# card_shield.net
KiCad netlist of a schematic drawn in EAGLE
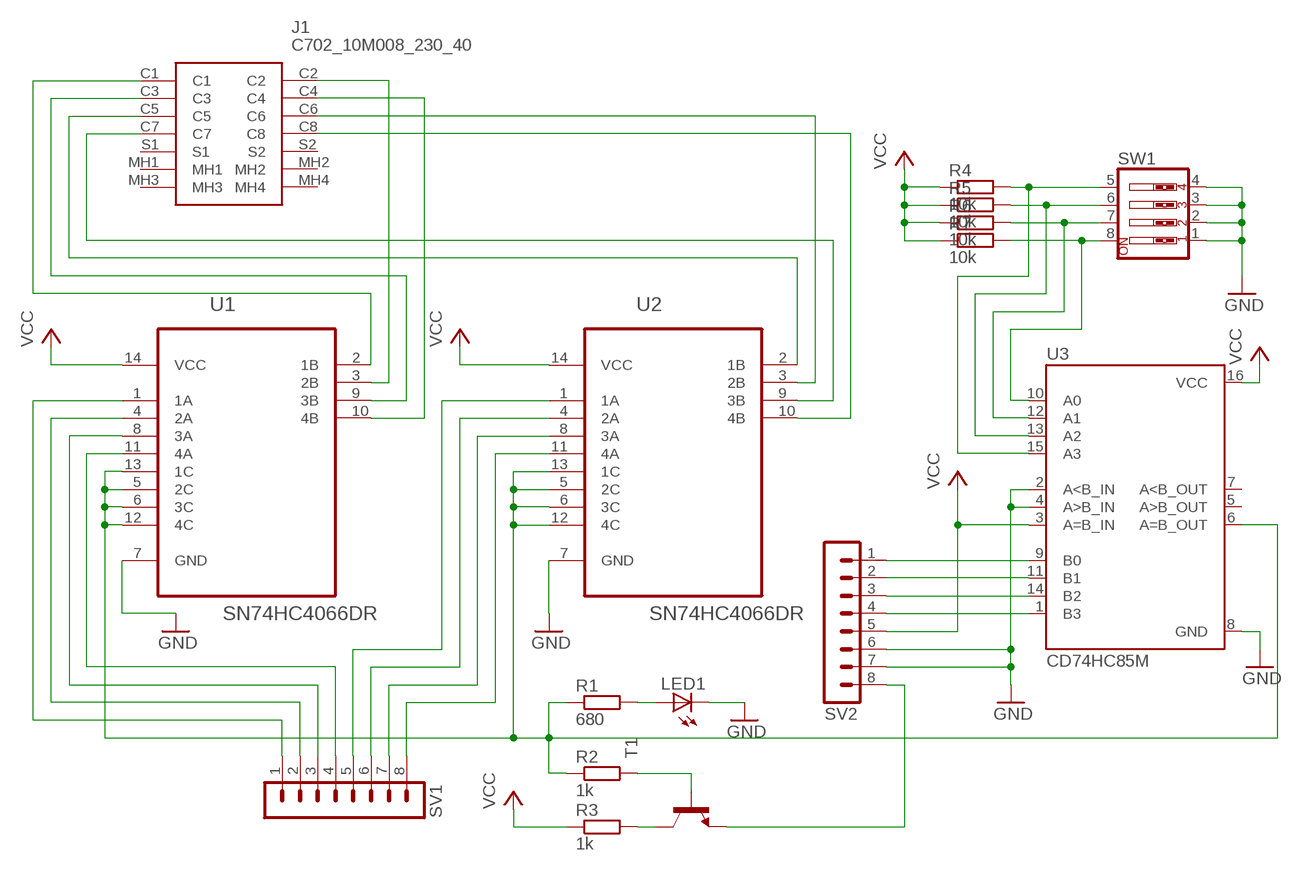
[diagram p0: schematic, sheet 1]

(export (version "E")
  (design (tool "Eeschema 10.0.6"))
  (components
    (comp (ref "J1")
      (value "C702_10M008_230_40")
      (footprint "eagle-import:C70210M00823040")
      (fields
        (field (name "MANUFACTURER_PART_NUMBER") "C702 10M008 230 40")
        (field (name "MOUSER_PART_NUMBER") "523-C70210M00823040")
      )
      (libsource (lib "eagle-import") (part "C702_10M008_230_40"))
    )
    (comp (ref "LED1")
      (value "LEDSML1206")
      (footprint "eagle-import:SML1206")
      (libsource (lib "eagle-import") (part "LEDSML1206"))
    )
    (comp (ref "R1")
      (value "680")
      (footprint "eagle-import:R0805")
      (libsource (lib "eagle-import") (part "R-EU_R0805"))
    )
    (comp (ref "R2")
      (value "1k")
      (footprint "eagle-import:R0805")
      (libsource (lib "eagle-import") (part "R-EU_R0805"))
    )
    (comp (ref "R3")
      (value "1k")
      (footprint "eagle-import:R0805")
      (libsource (lib "eagle-import") (part "R-EU_R0805"))
    )
    (comp (ref "R4")
      (value "10k")
      (footprint "eagle-import:R0805")
      (libsource (lib "eagle-import") (part "R-EU_R0805"))
    )
    (comp (ref "R5")
      (value "10k")
      (footprint "eagle-import:R0805")
      (libsource (lib "eagle-import") (part "R-EU_R0805"))
    )
    (comp (ref "R6")
      (value "10k")
      (footprint "eagle-import:R0805")
      (libsource (lib "eagle-import") (part "R-EU_R0805"))
    )
    (comp (ref "R7")
      (value "10k")
      (footprint "eagle-import:R0805")
      (libsource (lib "eagle-import") (part "R-EU_R0805"))
    )
    (comp (ref "SV1")
      (value "MA08-1")
      (footprint "eagle-import:MA08-1")
      (libsource (lib "eagle-import") (part "MA08-1"))
    )
    (comp (ref "SV2")
      (value "MA08-1")
      (footprint "eagle-import:MA08-1")
      (libsource (lib "eagle-import") (part "MA08-1"))
    )
    (comp (ref "SW1")
      (value "SW_DIP-4")
      (footprint "eagle-import:EDG-04")
      (libsource (lib "eagle-import") (part "SW_DIP-4"))
    )
    (comp (ref "T1")
      (value "BC817-16-NPN-SOT23-BEC")
      (footprint "eagle-import:SOT23-BEC")
      (libsource (lib "eagle-import") (part "-NPN-SOT23-BECBC817-16"))
    )
    (comp (ref "U1")
      (value "SN74HC4066DR")
      (footprint "eagle-import:SOIC127P600X175-14N")
      (fields (field (name "MF") "Texas Instruments"))
      (libsource (lib "eagle-import") (part "SN74HC4066DR"))
    )
    (comp (ref "U2")
      (value "SN74HC4066DR")
      (footprint "eagle-import:SOIC127P600X175-14N")
      (fields (field (name "MF") "Texas Instruments"))
      (libsource (lib "eagle-import") (part "SN74HC4066DR"))
    )
    (comp (ref "U3")
      (value "CD74HC85M")
      (footprint "eagle-import:SOIC12P600X175-16N")
      (fields (field (name "MF") "Texas Instruments"))
      (libsource (lib "eagle-import") (part "CD74HC85M"))
    )
  )
  (nets
    (net (code "1") (name "GND") (class "Default")
      (node (ref "LED1") (pin "C") (pinfunction "C_C") (pintype "passive"))
      (node (ref "SV2") (pin "6") (pinfunction "6_6") (pintype "passive"))
      (node (ref "SV2") (pin "7") (pinfunction "7_7") (pintype "passive"))
      (node (ref "SW1") (pin "1") (pinfunction "1_1") (pintype "passive"))
      (node (ref "SW1") (pin "2") (pinfunction "2_2") (pintype "passive"))
      (node (ref "SW1") (pin "3") (pinfunction "3_3") (pintype "passive"))
      (node (ref "SW1") (pin "4") (pinfunction "4_4") (pintype "passive"))
      (node (ref "U1") (pin "7") (pinfunction "GND_7") (pintype "passive"))
      (node (ref "U2") (pin "7") (pinfunction "GND_7") (pintype "passive"))
      (node (ref "U3") (pin "2") (pinfunction "A<B_IN_2") (pintype "input"))
      (node (ref "U3") (pin "4") (pinfunction "A>B_IN_4") (pintype "input"))
      (node (ref "U3") (pin "8") (pinfunction "GND_8") (pintype "power_in"))
    )
    (net (code "2") (name "Net-(LED1-PadA)") (class "Default")
      (node (ref "LED1") (pin "A") (pinfunction "A_A") (pintype "passive"))
      (node (ref "R1") (pin "2") (pinfunction "2_2") (pintype "passive"))
    )
    (net (code "3") (name "Net-(R2-Pad2)") (class "Default")
      (node (ref "R2") (pin "2") (pinfunction "2_2") (pintype "passive"))
      (node (ref "T1") (pin "B") (pinfunction "B_B") (pintype "passive"))
    )
    (net (code "4") (name "Net-(R3-Pad2)") (class "Default")
      (node (ref "R3") (pin "2") (pinfunction "2_2") (pintype "passive"))
      (node (ref "T1") (pin "C") (pinfunction "C_C") (pintype "passive"))
    )
    (net (code "5") (name "Net-(SV2-Pad8)") (class "Default")
      (node (ref "SV2") (pin "8") (pinfunction "8_8") (pintype "passive"))
      (node (ref "T1") (pin "E") (pinfunction "E_E") (pintype "passive"))
    )
    (net (code "6") (name "Net-(U1-1A)") (class "Default")
      (node (ref "SV1") (pin "1") (pinfunction "1_1") (pintype "passive"))
      (node (ref "U1") (pin "1") (pinfunction "1A_1") (pintype "input"))
    )
    (net (code "7") (name "Net-(U1-1B)") (class "Default")
      (node (ref "J1") (pin "C1") (pinfunction "C1_C1") (pintype "bidirectional"))
      (node (ref "U1") (pin "2") (pinfunction "1B_2") (pintype "output"))
    )
    (net (code "8") (name "Net-(U1-1C)") (class "Default")
      (node (ref "R1") (pin "1") (pinfunction "1_1") (pintype "passive"))
      (node (ref "R2") (pin "1") (pinfunction "1_1") (pintype "passive"))
      (node (ref "U1") (pin "12") (pinfunction "4C_12") (pintype "input"))
      (node (ref "U1") (pin "13") (pinfunction "1C_13") (pintype "input"))
      (node (ref "U1") (pin "5") (pinfunction "2C_5") (pintype "input"))
      (node (ref "U1") (pin "6") (pinfunction "3C_6") (pintype "input"))
      (node (ref "U2") (pin "12") (pinfunction "4C_12") (pintype "input"))
      (node (ref "U2") (pin "13") (pinfunction "1C_13") (pintype "input"))
      (node (ref "U2") (pin "5") (pinfunction "2C_5") (pintype "input"))
      (node (ref "U2") (pin "6") (pinfunction "3C_6") (pintype "input"))
      (node (ref "U3") (pin "6") (pinfunction "A=B_OUT_6") (pintype "output"))
    )
    (net (code "9") (name "Net-(U1-2A)") (class "Default")
      (node (ref "SV1") (pin "2") (pinfunction "2_2") (pintype "passive"))
      (node (ref "U1") (pin "4") (pinfunction "2A_4") (pintype "input"))
    )
    (net (code "10") (name "Net-(U1-2B)") (class "Default")
      (node (ref "J1") (pin "C2") (pinfunction "C2_C2") (pintype "bidirectional"))
      (node (ref "U1") (pin "3") (pinfunction "2B_3") (pintype "output"))
    )
    (net (code "11") (name "Net-(U1-3A)") (class "Default")
      (node (ref "SV1") (pin "3") (pinfunction "3_3") (pintype "passive"))
      (node (ref "U1") (pin "8") (pinfunction "3A_8") (pintype "input"))
    )
    (net (code "12") (name "Net-(U1-3B)") (class "Default")
      (node (ref "J1") (pin "C3") (pinfunction "C3_C3") (pintype "bidirectional"))
      (node (ref "U1") (pin "9") (pinfunction "3B_9") (pintype "output"))
    )
    (net (code "13") (name "Net-(U1-4A)") (class "Default")
      (node (ref "SV1") (pin "4") (pinfunction "4_4") (pintype "passive"))
      (node (ref "U1") (pin "11") (pinfunction "4A_11") (pintype "input"))
    )
    (net (code "14") (name "Net-(U1-4B)") (class "Default")
      (node (ref "J1") (pin "C4") (pinfunction "C4_C4") (pintype "bidirectional"))
      (node (ref "U1") (pin "10") (pinfunction "4B_10") (pintype "output"))
    )
    (net (code "15") (name "Net-(U2-1A)") (class "Default")
      (node (ref "SV1") (pin "5") (pinfunction "5_5") (pintype "passive"))
      (node (ref "U2") (pin "1") (pinfunction "1A_1") (pintype "input"))
    )
    (net (code "16") (name "Net-(U2-1B)") (class "Default")
      (node (ref "J1") (pin "C5") (pinfunction "C5_C5") (pintype "bidirectional"))
      (node (ref "U2") (pin "2") (pinfunction "1B_2") (pintype "output"))
    )
    (net (code "17") (name "Net-(U2-2A)") (class "Default")
      (node (ref "SV1") (pin "6") (pinfunction "6_6") (pintype "passive"))
      (node (ref "U2") (pin "4") (pinfunction "2A_4") (pintype "input"))
    )
    (net (code "18") (name "Net-(U2-2B)") (class "Default")
      (node (ref "J1") (pin "C6") (pinfunction "C6_C6") (pintype "bidirectional"))
      (node (ref "U2") (pin "3") (pinfunction "2B_3") (pintype "output"))
    )
    (net (code "19") (name "Net-(U2-3A)") (class "Default")
      (node (ref "SV1") (pin "7") (pinfunction "7_7") (pintype "passive"))
      (node (ref "U2") (pin "8") (pinfunction "3A_8") (pintype "input"))
    )
    (net (code "20") (name "Net-(U2-3B)") (class "Default")
      (node (ref "J1") (pin "C7") (pinfunction "C7_C7") (pintype "bidirectional"))
      (node (ref "U2") (pin "9") (pinfunction "3B_9") (pintype "output"))
    )
    (net (code "21") (name "Net-(U2-4A)") (class "Default")
      (node (ref "SV1") (pin "8") (pinfunction "8_8") (pintype "passive"))
      (node (ref "U2") (pin "11") (pinfunction "4A_11") (pintype "input"))
    )
    (net (code "22") (name "Net-(U2-4B)") (class "Default")
      (node (ref "J1") (pin "C8") (pinfunction "C8_C8") (pintype "bidirectional"))
      (node (ref "U2") (pin "10") (pinfunction "4B_10") (pintype "output"))
    )
    (net (code "23") (name "Net-(U3-A0)") (class "Default")
      (node (ref "R7") (pin "2") (pinfunction "2_2") (pintype "passive"))
      (node (ref "SW1") (pin "8") (pinfunction "8_8") (pintype "passive"))
      (node (ref "U3") (pin "10") (pinfunction "A0_10") (pintype "input"))
    )
    (net (code "24") (name "Net-(U3-A1)") (class "Default")
      (node (ref "R6") (pin "2") (pinfunction "2_2") (pintype "passive"))
      (node (ref "SW1") (pin "7") (pinfunction "7_7") (pintype "passive"))
      (node (ref "U3") (pin "12") (pinfunction "A1_12") (pintype "input"))
    )
    (net (code "25") (name "Net-(U3-A2)") (class "Default")
      (node (ref "R5") (pin "2") (pinfunction "2_2") (pintype "passive"))
      (node (ref "SW1") (pin "6") (pinfunction "6_6") (pintype "passive"))
      (node (ref "U3") (pin "13") (pinfunction "A2_13") (pintype "input"))
    )
    (net (code "26") (name "Net-(U3-A3)") (class "Default")
      (node (ref "R4") (pin "2") (pinfunction "2_2") (pintype "passive"))
      (node (ref "SW1") (pin "5") (pinfunction "5_5") (pintype "passive"))
      (node (ref "U3") (pin "15") (pinfunction "A3_15") (pintype "input"))
    )
    (net (code "27") (name "Net-(U3-B0)") (class "Default")
      (node (ref "SV2") (pin "1") (pinfunction "1_1") (pintype "passive"))
      (node (ref "U3") (pin "9") (pinfunction "B0_9") (pintype "input"))
    )
    (net (code "28") (name "Net-(U3-B1)") (class "Default")
      (node (ref "SV2") (pin "2") (pinfunction "2_2") (pintype "passive"))
      (node (ref "U3") (pin "11") (pinfunction "B1_11") (pintype "input"))
    )
    (net (code "29") (name "Net-(U3-B2)") (class "Default")
      (node (ref "SV2") (pin "3") (pinfunction "3_3") (pintype "passive"))
      (node (ref "U3") (pin "14") (pinfunction "B2_14") (pintype "input"))
    )
    (net (code "30") (name "Net-(U3-B3)") (class "Default")
      (node (ref "SV2") (pin "4") (pinfunction "4_4") (pintype "passive"))
      (node (ref "U3") (pin "1") (pinfunction "B3_1") (pintype "input"))
    )
    (net (code "31") (name "VCC") (class "Default")
      (node (ref "R3") (pin "1") (pinfunction "1_1") (pintype "passive"))
      (node (ref "R4") (pin "1") (pinfunction "1_1") (pintype "passive"))
      (node (ref "R5") (pin "1") (pinfunction "1_1") (pintype "passive"))
      (node (ref "R6") (pin "1") (pinfunction "1_1") (pintype "passive"))
      (node (ref "R7") (pin "1") (pinfunction "1_1") (pintype "passive"))
      (node (ref "SV2") (pin "5") (pinfunction "5_5") (pintype "passive"))
      (node (ref "U1") (pin "14") (pinfunction "VCC_14") (pintype "power_in"))
      (node (ref "U2") (pin "14") (pinfunction "VCC_14") (pintype "power_in"))
      (node (ref "U3") (pin "16") (pinfunction "VCC_16") (pintype "power_in"))
      (node (ref "U3") (pin "3") (pinfunction "A=B_IN_3") (pintype "input"))
    )
    (net (code "32") (name "unconnected-(J1-PadMH1)") (class "Default")
      (node (ref "J1") (pin "MH1") (pinfunction "MH1_MH1") (pintype "bidirectional"))
    )
    (net (code "33") (name "unconnected-(J1-PadMH2)") (class "Default")
      (node (ref "J1") (pin "MH2") (pinfunction "MH2_MH2") (pintype "bidirectional"))
    )
    (net (code "34") (name "unconnected-(J1-PadMH3)") (class "Default")
      (node (ref "J1") (pin "MH3") (pinfunction "MH3_MH3") (pintype "bidirectional"))
    )
    (net (code "35") (name "unconnected-(J1-PadMH4)") (class "Default")
      (node (ref "J1") (pin "MH4") (pinfunction "MH4_MH4") (pintype "bidirectional"))
    )
    (net (code "36") (name "unconnected-(J1-PadS1)") (class "Default")
      (node (ref "J1") (pin "S1") (pinfunction "S1_S1") (pintype "bidirectional"))
    )
    (net (code "37") (name "unconnected-(J1-PadS2)") (class "Default")
      (node (ref "J1") (pin "S2") (pinfunction "S2_S2") (pintype "bidirectional"))
    )
    (net (code "38") (name "unconnected-(U3-A<B_OUT-Pad7)") (class "Default")
      (node (ref "U3") (pin "7") (pinfunction "A<B_OUT_7") (pintype "output"))
    )
    (net (code "39") (name "unconnected-(U3-A>B_OUT-Pad5)") (class "Default")
      (node (ref "U3") (pin "5") (pinfunction "A>B_OUT_5") (pintype "output"))
    )
  )
)
